# BoardWithSeries.net
KiCad netlist of a schematic drawn in EAGLE
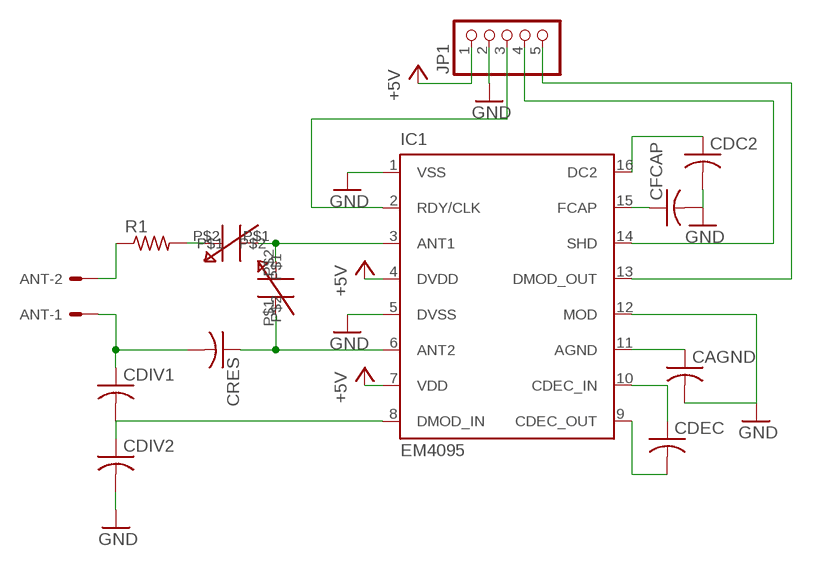
[diagram p0: schematic, sheet 1]

(export (version "E")
  (design (tool "Eeschema 10.0.6"))
  (components
    (comp (ref "ANT")
      (value "KK-156-2")
      (footprint "eagle-import:KK-156-2")
      (libsource (lib "eagle-import") (part "KK-156-2"))
    )
    (comp (ref "CAGND")
      (value "C-USC1206K")
      (footprint "eagle-import:C1206K")
      (libsource (lib "eagle-import") (part "C-USC1206K"))
    )
    (comp (ref "CDC2")
      (value "C-USC1206K")
      (footprint "eagle-import:C1206K")
      (libsource (lib "eagle-import") (part "C-USC1206K"))
    )
    (comp (ref "CDEC")
      (value "C-USC1206K")
      (footprint "eagle-import:C1206K")
      (libsource (lib "eagle-import") (part "C-USC1206K"))
    )
    (comp (ref "CDIV1")
      (value "C-USC1206K")
      (footprint "eagle-import:C1206K")
      (libsource (lib "eagle-import") (part "C-USC1206K"))
    )
    (comp (ref "CDIV2")
      (value "C-USC1206K")
      (footprint "eagle-import:C1206K")
      (libsource (lib "eagle-import") (part "C-USC1206K"))
    )
    (comp (ref "CFCAP")
      (value "C-USC1206K")
      (footprint "eagle-import:C1206K")
      (libsource (lib "eagle-import") (part "C-USC1206K"))
    )
    (comp (ref "CRES")
      (value "C-USC1206K")
      (footprint "eagle-import:C1206K")
      (libsource (lib "eagle-import") (part "C-USC1206K"))
    )
    (comp (ref "IC1")
      (value "EM4095")
      (footprint "eagle-import:SO16")
      (libsource (lib "eagle-import") (part "EM4095"))
    )
    (comp (ref "JP1")
      (value "PINHD-1X5")
      (footprint "eagle-import:1X05")
      (libsource (lib "eagle-import") (part "PINHD-1X5"))
    )
    (comp (ref "R1")
      (value "R-US_R1206")
      (footprint "eagle-import:R1206")
      (libsource (lib "eagle-import") (part "R-US_R1206"))
    )
    (comp (ref "U$1")
      (value "TZB4Z100AB10R00")
      (footprint "eagle-import:TZB4Z100AB10R00")
      (libsource (lib "eagle-import") (part "TZB4Z100AB10R00"))
    )
    (comp (ref "U$2")
      (value "TZB4Z100AB10R00")
      (footprint "eagle-import:TZB4Z100AB10R00")
      (libsource (lib "eagle-import") (part "TZB4Z100AB10R00"))
    )
  )
  (nets
    (net (code "1") (name "+5V") (class "Default")
      (node (ref "IC1") (pin "4") (pinfunction "DVDD_4") (pintype "power_in"))
      (node (ref "IC1") (pin "7") (pinfunction "VDD_7") (pintype "power_in"))
      (node (ref "JP1") (pin "1") (pinfunction "1_1") (pintype "passive"))
    )
    (net (code "2") (name "GND") (class "Default")
      (node (ref "CAGND") (pin "2") (pinfunction "2_2") (pintype "passive"))
      (node (ref "CDC2") (pin "2") (pinfunction "2_2") (pintype "passive"))
      (node (ref "CDIV2") (pin "2") (pinfunction "2_2") (pintype "passive"))
      (node (ref "CFCAP") (pin "2") (pinfunction "2_2") (pintype "passive"))
      (node (ref "IC1") (pin "1") (pinfunction "VSS_1") (pintype "power_in"))
      (node (ref "IC1") (pin "12") (pinfunction "MOD_12") (pintype "input"))
      (node (ref "IC1") (pin "5") (pinfunction "DVSS_5") (pintype "power_in"))
      (node (ref "JP1") (pin "2") (pinfunction "2_2") (pintype "passive"))
    )
    (net (code "3") (name "Net-(ANTA-S)") (class "Default")
      (node (ref "ANT") (pin "1") (pinfunction "S_1") (pintype "passive"))
      (node (ref "CDIV1") (pin "1") (pinfunction "1_1") (pintype "passive"))
      (node (ref "CRES") (pin "2") (pinfunction "2_2") (pintype "passive"))
    )
    (net (code "4") (name "Net-(ANTB-S)") (class "Default")
      (node (ref "ANT") (pin "2") (pinfunction "S_2") (pintype "passive"))
      (node (ref "R1") (pin "1") (pinfunction "1_1") (pintype "passive"))
    )
    (net (code "5") (name "Net-(IC1-AGND)") (class "Default")
      (node (ref "CAGND") (pin "1") (pinfunction "1_1") (pintype "passive"))
      (node (ref "IC1") (pin "11") (pinfunction "AGND_11") (pintype "power_in"))
    )
    (net (code "6") (name "Net-(IC1-ANT1)") (class "Default")
      (node (ref "IC1") (pin "3") (pinfunction "ANT1_3") (pintype "passive"))
      (node (ref "U$1") (pin "P$2") (pinfunction "P$2_P$2") (pintype "bidirectional"))
      (node (ref "U$2") (pin "P$1") (pinfunction "P$1_P$1") (pintype "bidirectional"))
    )
    (net (code "7") (name "Net-(IC1-ANT2)") (class "Default")
      (node (ref "CRES") (pin "1") (pinfunction "1_1") (pintype "passive"))
      (node (ref "IC1") (pin "6") (pinfunction "ANT2_6") (pintype "passive"))
      (node (ref "U$1") (pin "P$1") (pinfunction "P$1_P$1") (pintype "bidirectional"))
    )
    (net (code "8") (name "Net-(IC1-CDEC_IN)") (class "Default")
      (node (ref "CDEC") (pin "1") (pinfunction "1_1") (pintype "passive"))
      (node (ref "IC1") (pin "10") (pinfunction "CDEC_IN_10") (pintype "input"))
    )
    (net (code "9") (name "Net-(IC1-CDEC_OUT)") (class "Default")
      (node (ref "CDEC") (pin "2") (pinfunction "2_2") (pintype "passive"))
      (node (ref "IC1") (pin "9") (pinfunction "CDEC_OUT_9") (pintype "output"))
    )
    (net (code "10") (name "Net-(IC1-DC2)") (class "Default")
      (node (ref "CDC2") (pin "1") (pinfunction "1_1") (pintype "passive"))
      (node (ref "IC1") (pin "16") (pinfunction "DC2_16") (pintype "passive"))
    )
    (net (code "11") (name "Net-(IC1-DMOD_IN)") (class "Default")
      (node (ref "CDIV1") (pin "2") (pinfunction "2_2") (pintype "passive"))
      (node (ref "CDIV2") (pin "1") (pinfunction "1_1") (pintype "passive"))
      (node (ref "IC1") (pin "8") (pinfunction "DMOD_IN_8") (pintype "input"))
    )
    (net (code "12") (name "Net-(IC1-DMOD_OUT)") (class "Default")
      (node (ref "IC1") (pin "13") (pinfunction "DMOD_OUT_13") (pintype "output"))
      (node (ref "JP1") (pin "5") (pinfunction "5_5") (pintype "passive"))
    )
    (net (code "13") (name "Net-(IC1-FCAP)") (class "Default")
      (node (ref "CFCAP") (pin "1") (pinfunction "1_1") (pintype "passive"))
      (node (ref "IC1") (pin "15") (pinfunction "FCAP_15") (pintype "passive"))
    )
    (net (code "14") (name "Net-(IC1-RDY{slash}CLK)") (class "Default")
      (node (ref "IC1") (pin "2") (pinfunction "RDY/CLK_2") (pintype "output"))
      (node (ref "JP1") (pin "3") (pinfunction "3_3") (pintype "passive"))
    )
    (net (code "15") (name "Net-(IC1-SHD)") (class "Default")
      (node (ref "IC1") (pin "14") (pinfunction "SHD_14") (pintype "input"))
      (node (ref "JP1") (pin "4") (pinfunction "4_4") (pintype "passive"))
    )
    (net (code "16") (name "Net-(R1-Pad2)") (class "Default")
      (node (ref "R1") (pin "2") (pinfunction "2_2") (pintype "passive"))
      (node (ref "U$2") (pin "P$2") (pinfunction "P$2_P$2") (pintype "bidirectional"))
    )
  )
)
